# csi.net
KiCad netlist of a schematic drawn in Altium Designer
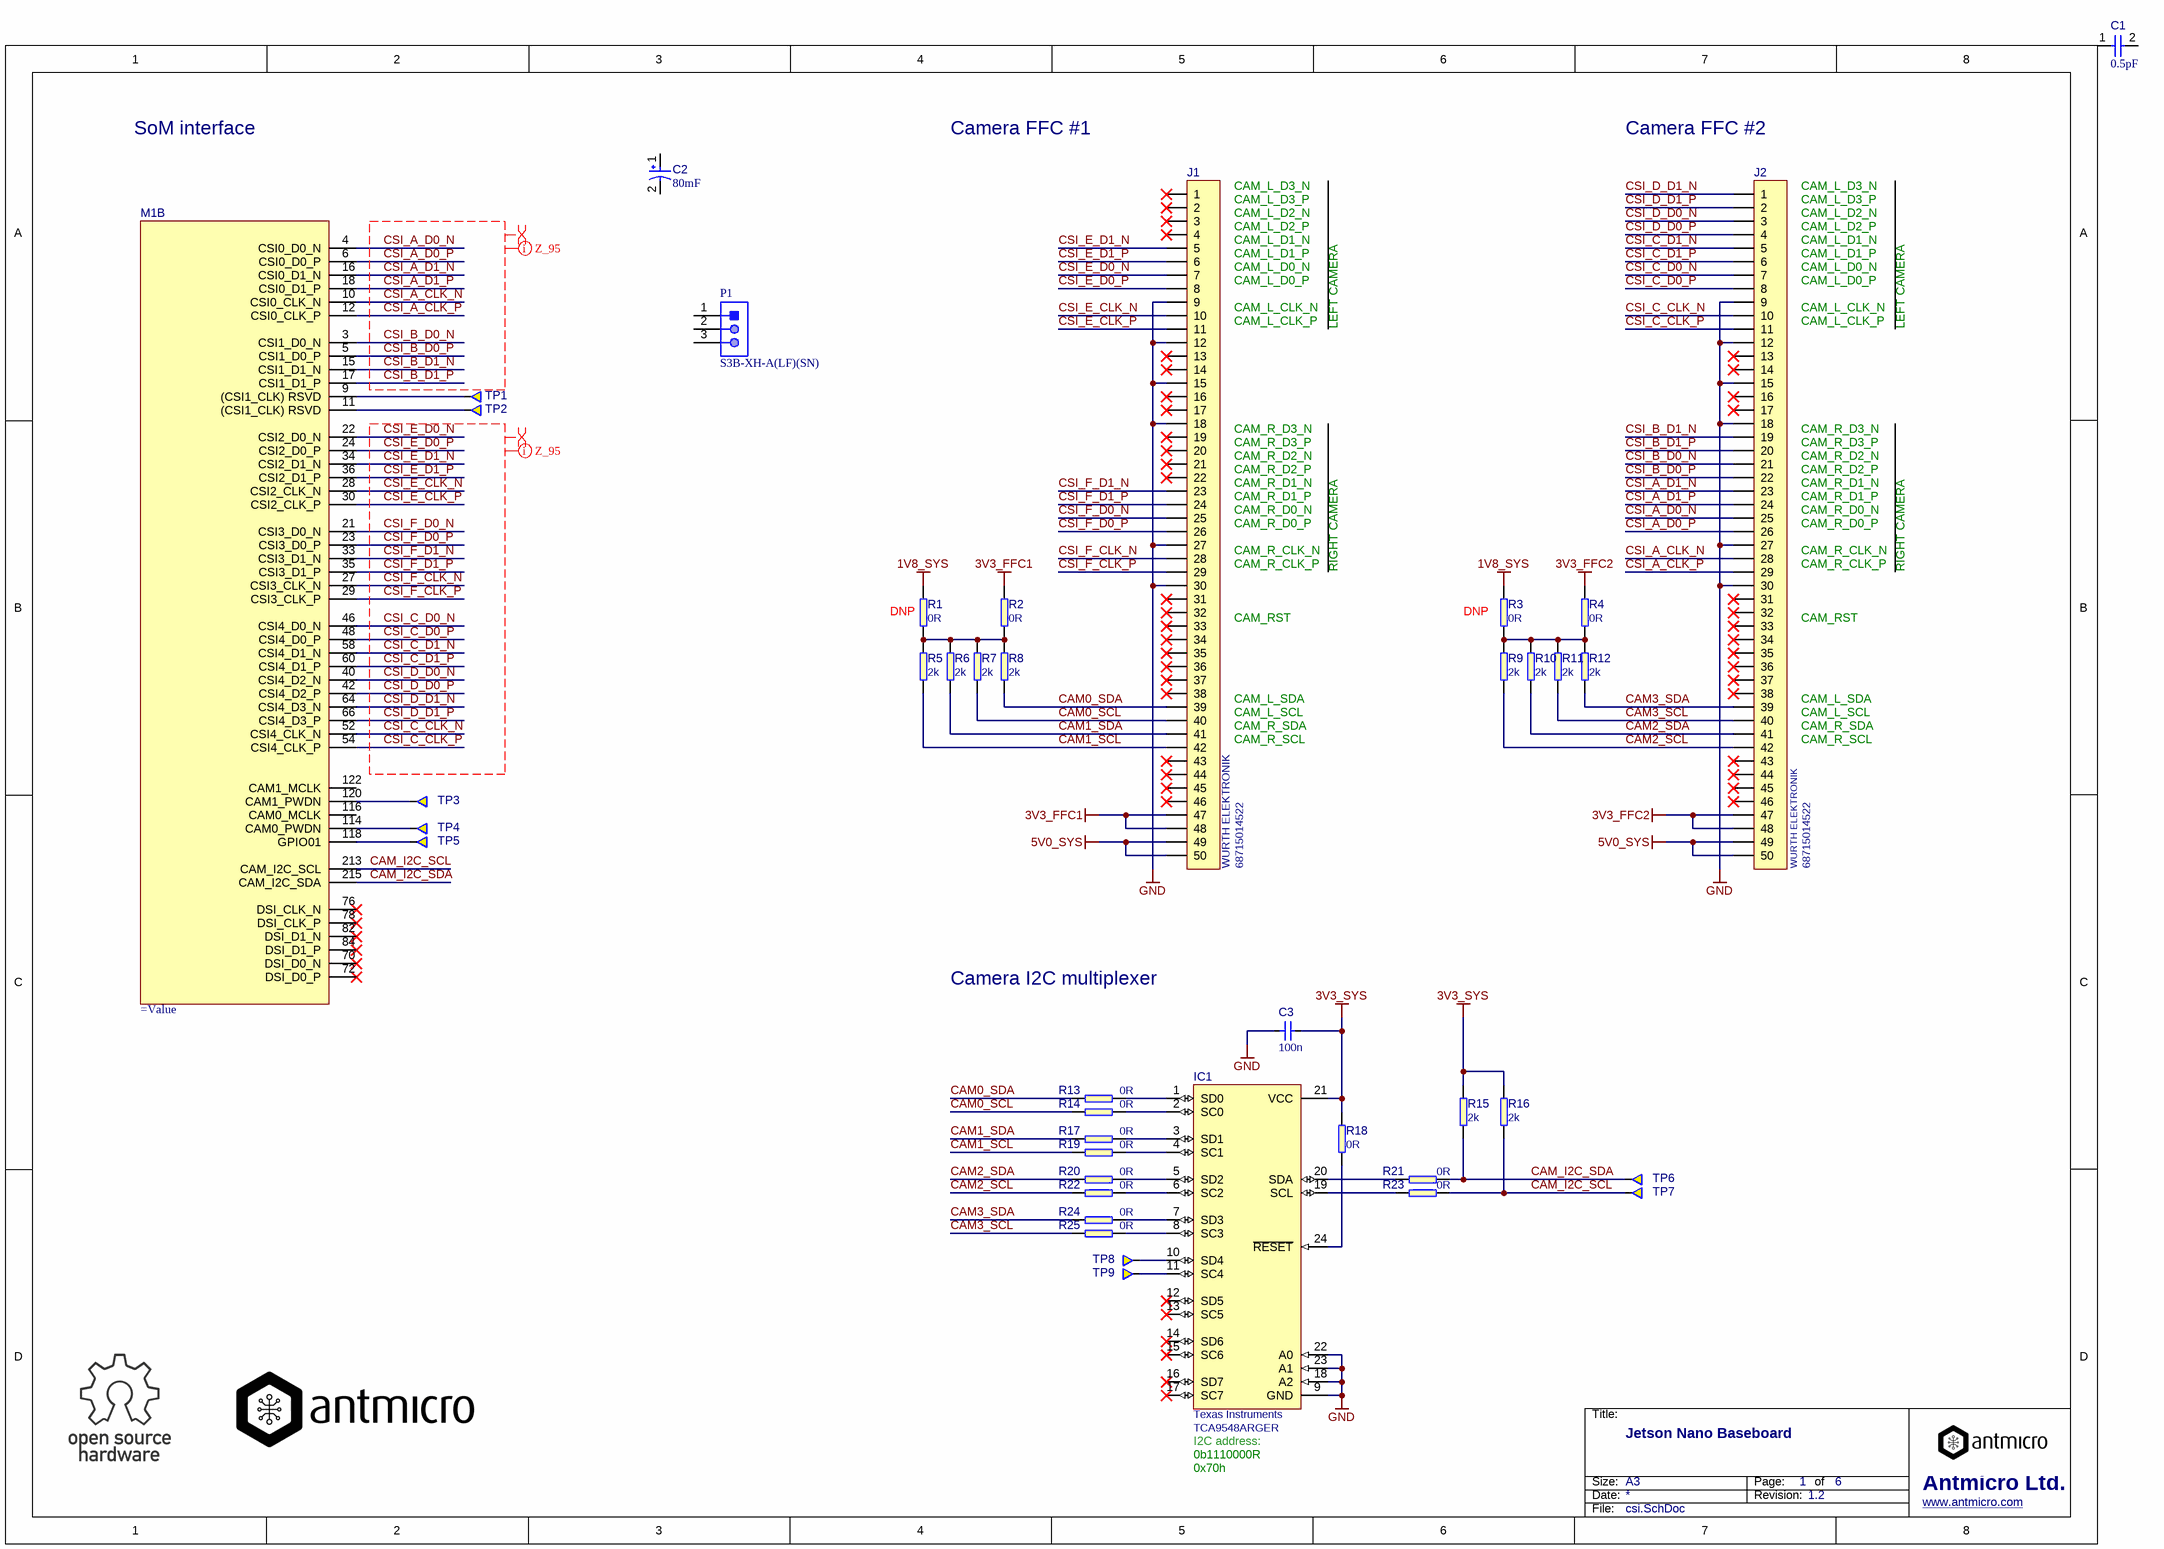
[diagram p0: csi.SchDoc]

(export (version "E")
  (design (tool "Eeschema 10.0.6"))
  (components
    (comp (ref "C1")
      (value "0.5pF")
      (footprint "CAPC1005X56X25ML10T15")
      (description "Chip Capacitor, 0.5 pF, +/- 0.1pF, 25 V, 0402 (1005 Metric)")
      (fields
        (field (name "TOLERANCE") "20%")
        (field (name "Comment") "Capacitor 0.5 pF +/- 0.1pF 25 V 0402")
      )
      (libsource (lib "ProtoTest2") (part "CAP-NP-2"))
    )
    (comp (ref "C2")
      (value "80mF")
      (footprint "SEIK-XH414HG-IV01E_V")
      (description "Electric Double Layer Capacitor, 80 mF, 3.3 V, -20 to 60 degC, RoHS")
      (fields (field (name "MANUFACTURER") "Seiko Instruments") (field (name "Comment") "XH414HG-IV01E"))
      (libsource (lib "ProtoTest2") (part "CAP-P-2"))
    )
    (comp (ref "C3")
      (value "100n")
      (footprint "0402")
      (description "MLCC SMT Capacitor 100n 0402")
      (fields (field (name "MANUFACTURER") "TDK") (field (name "PARTNUMBER") "C_100n_0402"))
      (libsource (lib "jetson-nano-baseboard") (part "C_100n_0402"))
    )
    (comp (ref "IC1")
      (value "TCA9548ARGER")
      (footprint "VQFN-24")
      (description "TCA9548ARGER  I2C SWITCH W/ RESET, 8-CH, VQFN-24")
      (fields (field (name "MANUFACTURER") "Texas Instruments"))
      (libsource (lib "jetson-nano-baseboard") (part "TCA9548A"))
    )
    (comp (ref "J1")
      (value "68715014522")
      (footprint "68715014522")
      (description "0.50mm SMT ZIF Horizontal Bottom Contact WR-FPC")
      (fields
        (field (name "MANUFACTURER") "WURTH ELEKTRONIK")
        (field (name "PARTNUMBER") "WE-687-150-145-22")
      )
      (libsource (lib "jetson-nano-baseboard") (part "1X50"))
    )
    (comp (ref "J2")
      (value "68715014522")
      (footprint "68715014522")
      (description "0.50mm SMT ZIF Horizontal Bottom Contact WR-FPC")
      (fields
        (field (name "PARTNUMBER") "WE-687-150-145-22")
        (field (name "MANUFACTURER") "WURTH ELEKTRONIK")
      )
      (libsource (lib "jetson-nano-baseboard") (part "1X50"))
    )
    (comp (ref "M1")
      (value "~")
      (footprint "jetson-nano-connector")
      (fields (field (name "PARTNUMBER") "jetson-nano-new-release"))
      (libsource (lib "jetson-nano-baseboard") (part "Jetson-Nano-new-release"))
    )
    (comp (ref "P1")
      (value "S3B-XH-A(LF)(SN)")
      (footprint "JST-S3B-XH-A(LF)(SN)_V")
      (fields (field (name "MANUFACTURER") "JST"))
      (libsource (lib "ProtoTest2") (part "CN-1P-M-R3"))
    )
    (comp (ref "R1")
      (value "0R")
      (footprint "0402")
      (description "RES, 0R, 0402")
      (fields (field (name "MANUFACTURER") "Panasonic") (field (name "PARTNUMBER") "R_0R_0402"))
      (libsource (lib "") (part "R_0R_0402_1"))
    )
    (comp (ref "R2")
      (value "0R")
      (footprint "0402")
      (description "RES, 0R, 0402")
      (fields (field (name "MANUFACTURER") "Panasonic") (field (name "PARTNUMBER") "R_0R_0402"))
      (libsource (lib "") (part "R_0R_0402_1"))
    )
    (comp (ref "R3")
      (value "0R")
      (footprint "0402")
      (description "RES, 0R, 0402")
      (fields (field (name "MANUFACTURER") "Panasonic") (field (name "PARTNUMBER") "R_0R_0402"))
      (libsource (lib "") (part "R_0R_0402_1"))
    )
    (comp (ref "R4")
      (value "0R")
      (footprint "0402")
      (description "RES, 0R, 0402")
      (fields (field (name "MANUFACTURER") "Panasonic") (field (name "PARTNUMBER") "R_0R_0402"))
      (libsource (lib "") (part "R_0R_0402_1"))
    )
    (comp (ref "R5")
      (value "2k")
      (footprint "0402")
      (description "RES, 2k, 0402")
      (fields (field (name "PARTNUMBER") "R_2k_0402") (field (name "MANUFACTURER") "VISHAY"))
      (libsource (lib "jetson-nano-baseboard") (part "R_2k_0402"))
    )
    (comp (ref "R6")
      (value "2k")
      (footprint "0402")
      (description "RES, 2k, 0402")
      (fields (field (name "PARTNUMBER") "R_2k_0402") (field (name "MANUFACTURER") "VISHAY"))
      (libsource (lib "jetson-nano-baseboard") (part "R_2k_0402"))
    )
    (comp (ref "R7")
      (value "2k")
      (footprint "0402")
      (description "RES, 2k, 0402")
      (fields (field (name "PARTNUMBER") "R_2k_0402") (field (name "MANUFACTURER") "VISHAY"))
      (libsource (lib "jetson-nano-baseboard") (part "R_2k_0402"))
    )
    (comp (ref "R8")
      (value "2k")
      (footprint "0402")
      (description "RES, 2k, 0402")
      (fields (field (name "PARTNUMBER") "R_2k_0402") (field (name "MANUFACTURER") "VISHAY"))
      (libsource (lib "jetson-nano-baseboard") (part "R_2k_0402"))
    )
    (comp (ref "R9")
      (value "2k")
      (footprint "0402")
      (description "RES, 2k, 0402")
      (fields (field (name "PARTNUMBER") "R_2k_0402") (field (name "MANUFACTURER") "VISHAY"))
      (libsource (lib "jetson-nano-baseboard") (part "R_2k_0402"))
    )
    (comp (ref "R10")
      (value "2k")
      (footprint "0402")
      (description "RES, 2k, 0402")
      (fields (field (name "PARTNUMBER") "R_2k_0402") (field (name "MANUFACTURER") "VISHAY"))
      (libsource (lib "jetson-nano-baseboard") (part "R_2k_0402"))
    )
    (comp (ref "R11")
      (value "2k")
      (footprint "0402")
      (description "RES, 2k, 0402")
      (fields (field (name "PARTNUMBER") "R_2k_0402") (field (name "MANUFACTURER") "VISHAY"))
      (libsource (lib "jetson-nano-baseboard") (part "R_2k_0402"))
    )
    (comp (ref "R12")
      (value "2k")
      (footprint "0402")
      (description "RES, 2k, 0402")
      (fields (field (name "PARTNUMBER") "R_2k_0402") (field (name "MANUFACTURER") "VISHAY"))
      (libsource (lib "jetson-nano-baseboard") (part "R_2k_0402"))
    )
    (comp (ref "R13")
      (value "0R")
      (footprint "0402")
      (description "RES, 0R, 0402")
      (fields (field (name "MANUFACTURER") "Panasonic") (field (name "PARTNUMBER") "R_0R_0402"))
      (libsource (lib "jetson-nano-baseboard") (part "R_0R_0402"))
    )
    (comp (ref "R14")
      (value "0R")
      (footprint "0402")
      (description "RES, 0R, 0402")
      (fields (field (name "MANUFACTURER") "Panasonic") (field (name "PARTNUMBER") "R_0R_0402"))
      (libsource (lib "jetson-nano-baseboard") (part "R_0R_0402"))
    )
    (comp (ref "R15")
      (value "2k")
      (footprint "0402")
      (description "RES, 2k, 0402")
      (fields (field (name "PARTNUMBER") "R_2k_0402") (field (name "MANUFACTURER") "VISHAY"))
      (libsource (lib "jetson-nano-baseboard") (part "R_2k_0402"))
    )
    (comp (ref "R16")
      (value "2k")
      (footprint "0402")
      (description "RES, 2k, 0402")
      (fields (field (name "PARTNUMBER") "R_2k_0402") (field (name "MANUFACTURER") "VISHAY"))
      (libsource (lib "jetson-nano-baseboard") (part "R_2k_0402"))
    )
    (comp (ref "R17")
      (value "0R")
      (footprint "0402")
      (description "RES, 0R, 0402")
      (fields (field (name "MANUFACTURER") "Panasonic") (field (name "PARTNUMBER") "R_0R_0402"))
      (libsource (lib "jetson-nano-baseboard") (part "R_0R_0402"))
    )
    (comp (ref "R18")
      (value "0R")
      (footprint "0402")
      (description "RES, 0R, 0402")
      (fields (field (name "MANUFACTURER") "Panasonic") (field (name "PARTNUMBER") "R_0R_0402"))
      (libsource (lib "") (part "R_0R_0402_1"))
    )
    (comp (ref "R19")
      (value "0R")
      (footprint "0402")
      (description "RES, 0R, 0402")
      (fields (field (name "MANUFACTURER") "Panasonic") (field (name "PARTNUMBER") "R_0R_0402"))
      (libsource (lib "jetson-nano-baseboard") (part "R_0R_0402"))
    )
    (comp (ref "R20")
      (value "0R")
      (footprint "0402")
      (description "RES, 0R, 0402")
      (fields (field (name "MANUFACTURER") "Panasonic") (field (name "PARTNUMBER") "R_0R_0402"))
      (libsource (lib "jetson-nano-baseboard") (part "R_0R_0402"))
    )
    (comp (ref "R21")
      (value "0R")
      (footprint "0402")
      (description "RES, 0R, 0402")
      (fields (field (name "MANUFACTURER") "Panasonic") (field (name "PARTNUMBER") "R_0R_0402"))
      (libsource (lib "jetson-nano-baseboard") (part "R_0R_0402"))
    )
    (comp (ref "R22")
      (value "0R")
      (footprint "0402")
      (description "RES, 0R, 0402")
      (fields (field (name "MANUFACTURER") "Panasonic") (field (name "PARTNUMBER") "R_0R_0402"))
      (libsource (lib "jetson-nano-baseboard") (part "R_0R_0402"))
    )
    (comp (ref "R23")
      (value "0R")
      (footprint "0402")
      (description "RES, 0R, 0402")
      (fields (field (name "MANUFACTURER") "Panasonic") (field (name "PARTNUMBER") "R_0R_0402"))
      (libsource (lib "jetson-nano-baseboard") (part "R_0R_0402"))
    )
    (comp (ref "R24")
      (value "0R")
      (footprint "0402")
      (description "RES, 0R, 0402")
      (fields (field (name "MANUFACTURER") "Panasonic") (field (name "PARTNUMBER") "R_0R_0402"))
      (libsource (lib "jetson-nano-baseboard") (part "R_0R_0402"))
    )
    (comp (ref "R25")
      (value "0R")
      (footprint "0402")
      (description "RES, 0R, 0402")
      (fields (field (name "MANUFACTURER") "Panasonic") (field (name "PARTNUMBER") "R_0R_0402"))
      (libsource (lib "jetson-nano-baseboard") (part "R_0R_0402"))
    )
    (comp (ref "TP1")
      (value "Testpad")
      (footprint "TP-R-1.5")
      (description "Testpad, round, 1.5mm")
      (fields (field (name "PARTNUMBER") "TP-R-1.5"))
      (libsource (lib "jetson-nano-baseboard") (part "Testpad"))
    )
    (comp (ref "TP2")
      (value "Testpad")
      (footprint "TP-R-1.5")
      (description "Testpad, round, 1.5mm")
      (fields (field (name "PARTNUMBER") "TP-R-1.5"))
      (libsource (lib "jetson-nano-baseboard") (part "Testpad"))
    )
    (comp (ref "TP3")
      (value "Testpad")
      (footprint "TP-R-1.5")
      (description "Testpad, round, 1.5mm")
      (fields (field (name "PARTNUMBER") "TP-R-1.5"))
      (libsource (lib "jetson-nano-baseboard") (part "Testpad"))
    )
    (comp (ref "TP4")
      (value "Testpad")
      (footprint "TP-R-1.5")
      (description "Testpad, round, 1.5mm")
      (fields (field (name "PARTNUMBER") "TP-R-1.5"))
      (libsource (lib "jetson-nano-baseboard") (part "Testpad"))
    )
    (comp (ref "TP5")
      (value "Testpad")
      (footprint "TP-R-1.5")
      (description "Testpad, round, 1.5mm")
      (fields (field (name "PARTNUMBER") "TP-R-1.5"))
      (libsource (lib "jetson-nano-baseboard") (part "Testpad"))
    )
    (comp (ref "TP6")
      (value "Testpad")
      (footprint "TP-R-1.5")
      (description "Testpad, round, 1.5mm")
      (fields (field (name "PARTNUMBER") "TP-R-1.5"))
      (libsource (lib "jetson-nano-baseboard") (part "Testpad"))
    )
    (comp (ref "TP7")
      (value "Testpad")
      (footprint "TP-R-1.5")
      (description "Testpad, round, 1.5mm")
      (fields (field (name "PARTNUMBER") "TP-R-1.5"))
      (libsource (lib "jetson-nano-baseboard") (part "Testpad"))
    )
    (comp (ref "TP8")
      (value "Testpad")
      (footprint "TP-R-1.5")
      (description "Testpad, round, 1.5mm")
      (fields (field (name "PARTNUMBER") "TP-R-1.5"))
      (libsource (lib "jetson-nano-baseboard") (part "Testpad"))
    )
    (comp (ref "TP9")
      (value "Testpad")
      (footprint "TP-R-1.5")
      (description "Testpad, round, 1.5mm")
      (fields (field (name "PARTNUMBER") "TP-R-1.5"))
      (libsource (lib "jetson-nano-baseboard") (part "Testpad"))
    )
  )
  (nets
    (net (code "1") (name "/CAM0_SCL") (class "Default")
      (node (ref "J1") (pin "40") (pinfunction "40_40") (pintype "passive"))
      (node (ref "R14") (pin "1") (pintype "passive"))
      (node (ref "R7") (pin "2") (pintype "passive"))
    )
    (net (code "2") (name "/CAM0_SDA") (class "Default")
      (node (ref "J1") (pin "39") (pinfunction "39_39") (pintype "passive"))
      (node (ref "R13") (pin "1") (pintype "passive"))
      (node (ref "R8") (pin "2") (pintype "passive"))
    )
    (net (code "3") (name "/CAM1_SCL") (class "Default")
      (node (ref "J1") (pin "42") (pinfunction "42_42") (pintype "passive"))
      (node (ref "R19") (pin "1") (pintype "passive"))
      (node (ref "R5") (pin "2") (pintype "passive"))
    )
    (net (code "4") (name "/CAM1_SDA") (class "Default")
      (node (ref "J1") (pin "41") (pinfunction "41_41") (pintype "passive"))
      (node (ref "R17") (pin "1") (pintype "passive"))
      (node (ref "R6") (pin "2") (pintype "passive"))
    )
    (net (code "5") (name "/CAM2_SCL") (class "Default")
      (node (ref "J2") (pin "42") (pinfunction "42_42") (pintype "passive"))
      (node (ref "R22") (pin "1") (pintype "passive"))
      (node (ref "R9") (pin "2") (pintype "passive"))
    )
    (net (code "6") (name "/CAM2_SDA") (class "Default")
      (node (ref "J2") (pin "41") (pinfunction "41_41") (pintype "passive"))
      (node (ref "R10") (pin "2") (pintype "passive"))
      (node (ref "R20") (pin "1") (pintype "passive"))
    )
    (net (code "7") (name "/CAM3_SCL") (class "Default")
      (node (ref "J2") (pin "40") (pinfunction "40_40") (pintype "passive"))
      (node (ref "R11") (pin "2") (pintype "passive"))
      (node (ref "R25") (pin "1") (pintype "passive"))
    )
    (net (code "8") (name "/CAM3_SDA") (class "Default")
      (node (ref "J2") (pin "39") (pinfunction "39_39") (pintype "passive"))
      (node (ref "R12") (pin "2") (pintype "passive"))
      (node (ref "R24") (pin "1") (pintype "passive"))
    )
    (net (code "9") (name "/CAM_I2C_SCL") (class "Default")
      (node (ref "M1") (pin "213") (pinfunction "CAM_I2C_SCL_213") (pintype "passive"))
      (node (ref "R16") (pin "2") (pintype "passive"))
      (node (ref "R23") (pin "2") (pintype "passive"))
      (node (ref "TP7") (pin "1") (pintype "passive"))
    )
    (net (code "10") (name "/CAM_I2C_SDA") (class "Default")
      (node (ref "M1") (pin "215") (pinfunction "CAM_I2C_SDA_215") (pintype "passive"))
      (node (ref "R15") (pin "2") (pintype "passive"))
      (node (ref "R21") (pin "2") (pintype "passive"))
      (node (ref "TP6") (pin "1") (pintype "passive"))
    )
    (net (code "11") (name "/CSI_A_CLK_N") (class "Default")
      (node (ref "J2") (pin "28") (pinfunction "28_28") (pintype "passive"))
      (node (ref "M1") (pin "10") (pinfunction "CSI0_CLK_N_10") (pintype "passive"))
    )
    (net (code "12") (name "/CSI_A_CLK_P") (class "Default")
      (node (ref "J2") (pin "29") (pinfunction "29_29") (pintype "passive"))
      (node (ref "M1") (pin "12") (pinfunction "CSI0_CLK_P_12") (pintype "passive"))
    )
    (net (code "13") (name "/CSI_A_D0_N") (class "Default")
      (node (ref "J2") (pin "25") (pinfunction "25_25") (pintype "passive"))
      (node (ref "M1") (pin "4") (pinfunction "CSI0_D0_N_4") (pintype "passive"))
    )
    (net (code "14") (name "/CSI_A_D0_P") (class "Default")
      (node (ref "J2") (pin "26") (pinfunction "26_26") (pintype "passive"))
      (node (ref "M1") (pin "6") (pinfunction "CSI0_D0_P_6") (pintype "passive"))
    )
    (net (code "15") (name "/CSI_A_D1_N") (class "Default")
      (node (ref "J2") (pin "23") (pinfunction "23_23") (pintype "passive"))
      (node (ref "M1") (pin "16") (pinfunction "CSI0_D1_N_16") (pintype "passive"))
    )
    (net (code "16") (name "/CSI_A_D1_P") (class "Default")
      (node (ref "J2") (pin "24") (pinfunction "24_24") (pintype "passive"))
      (node (ref "M1") (pin "18") (pinfunction "CSI0_D1_P_18") (pintype "passive"))
    )
    (net (code "17") (name "/CSI_B_D0_N") (class "Default")
      (node (ref "J2") (pin "21") (pinfunction "21_21") (pintype "passive"))
      (node (ref "M1") (pin "3") (pinfunction "CSI1_D0_N_3") (pintype "passive"))
    )
    (net (code "18") (name "/CSI_B_D0_P") (class "Default")
      (node (ref "J2") (pin "22") (pinfunction "22_22") (pintype "passive"))
      (node (ref "M1") (pin "5") (pinfunction "CSI1_D0_P_5") (pintype "passive"))
    )
    (net (code "19") (name "/CSI_B_D1_N") (class "Default")
      (node (ref "J2") (pin "19") (pinfunction "19_19") (pintype "passive"))
      (node (ref "M1") (pin "15") (pinfunction "CSI1_D1_N_15") (pintype "passive"))
    )
    (net (code "20") (name "/CSI_B_D1_P") (class "Default")
      (node (ref "J2") (pin "20") (pinfunction "20_20") (pintype "passive"))
      (node (ref "M1") (pin "17") (pinfunction "CSI1_D1_P_17") (pintype "passive"))
    )
    (net (code "21") (name "/CSI_C_CLK_N") (class "Default")
      (node (ref "J2") (pin "10") (pinfunction "10_10") (pintype "passive"))
      (node (ref "M1") (pin "52") (pinfunction "CSI4_CLK_N_52") (pintype "passive"))
    )
    (net (code "22") (name "/CSI_C_CLK_P") (class "Default")
      (node (ref "J2") (pin "11") (pinfunction "11_11") (pintype "passive"))
      (node (ref "M1") (pin "54") (pinfunction "CSI4_CLK_P_54") (pintype "passive"))
    )
    (net (code "23") (name "/CSI_C_D0_N") (class "Default")
      (node (ref "J2") (pin "7") (pinfunction "7_7") (pintype "passive"))
      (node (ref "M1") (pin "46") (pinfunction "CSI4_D0_N_46") (pintype "passive"))
    )
    (net (code "24") (name "/CSI_C_D0_P") (class "Default")
      (node (ref "J2") (pin "8") (pinfunction "8_8") (pintype "passive"))
      (node (ref "M1") (pin "48") (pinfunction "CSI4_D0_P_48") (pintype "passive"))
    )
    (net (code "25") (name "/CSI_C_D1_N") (class "Default")
      (node (ref "J2") (pin "5") (pinfunction "5_5") (pintype "passive"))
      (node (ref "M1") (pin "58") (pinfunction "CSI4_D1_N_58") (pintype "passive"))
    )
    (net (code "26") (name "/CSI_C_D1_P") (class "Default")
      (node (ref "J2") (pin "6") (pinfunction "6_6") (pintype "passive"))
      (node (ref "M1") (pin "60") (pinfunction "CSI4_D1_P_60") (pintype "passive"))
    )
    (net (code "27") (name "/CSI_D_D0_N") (class "Default")
      (node (ref "J2") (pin "3") (pinfunction "3_3") (pintype "passive"))
      (node (ref "M1") (pin "40") (pinfunction "CSI4_D2_N_40") (pintype "passive"))
    )
    (net (code "28") (name "/CSI_D_D0_P") (class "Default")
      (node (ref "J2") (pin "4") (pinfunction "4_4") (pintype "passive"))
      (node (ref "M1") (pin "42") (pinfunction "CSI4_D2_P_42") (pintype "passive"))
    )
    (net (code "29") (name "/CSI_D_D1_N") (class "Default")
      (node (ref "J2") (pin "1") (pinfunction "1_1") (pintype "passive"))
      (node (ref "M1") (pin "64") (pinfunction "CSI4_D3_N_64") (pintype "passive"))
    )
    (net (code "30") (name "/CSI_D_D1_P") (class "Default")
      (node (ref "J2") (pin "2") (pinfunction "2_2") (pintype "passive"))
      (node (ref "M1") (pin "66") (pinfunction "CSI4_D3_P_66") (pintype "passive"))
    )
    (net (code "31") (name "/CSI_E_CLK_N") (class "Default")
      (node (ref "J1") (pin "10") (pinfunction "10_10") (pintype "passive"))
      (node (ref "M1") (pin "28") (pinfunction "CSI2_CLK_N_28") (pintype "passive"))
    )
    (net (code "32") (name "/CSI_E_CLK_P") (class "Default")
      (node (ref "J1") (pin "11") (pinfunction "11_11") (pintype "passive"))
      (node (ref "M1") (pin "30") (pinfunction "CSI2_CLK_P_30") (pintype "passive"))
    )
    (net (code "33") (name "/CSI_E_D0_N") (class "Default")
      (node (ref "J1") (pin "7") (pinfunction "7_7") (pintype "passive"))
      (node (ref "M1") (pin "22") (pinfunction "CSI2_D0_N_22") (pintype "passive"))
    )
    (net (code "34") (name "/CSI_E_D0_P") (class "Default")
      (node (ref "J1") (pin "8") (pinfunction "8_8") (pintype "passive"))
      (node (ref "M1") (pin "24") (pinfunction "CSI2_D0_P_24") (pintype "passive"))
    )
    (net (code "35") (name "/CSI_E_D1_N") (class "Default")
      (node (ref "J1") (pin "5") (pinfunction "5_5") (pintype "passive"))
      (node (ref "M1") (pin "34") (pinfunction "CSI2_D1_N_34") (pintype "passive"))
    )
    (net (code "36") (name "/CSI_E_D1_P") (class "Default")
      (node (ref "J1") (pin "6") (pinfunction "6_6") (pintype "passive"))
      (node (ref "M1") (pin "36") (pinfunction "CSI2_D1_P_36") (pintype "passive"))
    )
    (net (code "37") (name "/CSI_F_CLK_N") (class "Default")
      (node (ref "J1") (pin "28") (pinfunction "28_28") (pintype "passive"))
      (node (ref "M1") (pin "27") (pinfunction "CSI3_CLK_N_27") (pintype "passive"))
    )
    (net (code "38") (name "/CSI_F_CLK_P") (class "Default")
      (node (ref "J1") (pin "29") (pinfunction "29_29") (pintype "passive"))
      (node (ref "M1") (pin "29") (pinfunction "CSI3_CLK_P_29") (pintype "passive"))
    )
    (net (code "39") (name "/CSI_F_D0_N") (class "Default")
      (node (ref "J1") (pin "25") (pinfunction "25_25") (pintype "passive"))
      (node (ref "M1") (pin "21") (pinfunction "CSI3_D0_N_21") (pintype "passive"))
    )
    (net (code "40") (name "/CSI_F_D0_P") (class "Default")
      (node (ref "J1") (pin "26") (pinfunction "26_26") (pintype "passive"))
      (node (ref "M1") (pin "23") (pinfunction "CSI3_D0_P_23") (pintype "passive"))
    )
    (net (code "41") (name "/CSI_F_D1_N") (class "Default")
      (node (ref "J1") (pin "23") (pinfunction "23_23") (pintype "passive"))
      (node (ref "M1") (pin "33") (pinfunction "CSI3_D1_N_33") (pintype "passive"))
    )
    (net (code "42") (name "/CSI_F_D1_P") (class "Default")
      (node (ref "J1") (pin "24") (pinfunction "24_24") (pintype "passive"))
      (node (ref "M1") (pin "35") (pinfunction "CSI3_D1_P_35") (pintype "passive"))
    )
    (net (code "43") (name "1V8_SYS") (class "Default")
      (node (ref "R1") (pin "2") (pintype "passive"))
      (node (ref "R3") (pin "2") (pintype "passive"))
    )
    (net (code "44") (name "3V3_FFC1") (class "Default")
      (node (ref "J1") (pin "47") (pinfunction "47_47") (pintype "passive"))
      (node (ref "J1") (pin "48") (pinfunction "48_48") (pintype "passive"))
      (node (ref "R2") (pin "2") (pintype "passive"))
    )
    (net (code "45") (name "3V3_FFC2") (class "Default")
      (node (ref "J2") (pin "47") (pinfunction "47_47") (pintype "passive"))
      (node (ref "J2") (pin "48") (pinfunction "48_48") (pintype "passive"))
      (node (ref "R4") (pin "2") (pintype "passive"))
    )
    (net (code "46") (name "3V3_SYS") (class "Default")
      (node (ref "C3") (pin "2") (pinfunction "2_2") (pintype "passive"))
      (node (ref "IC1") (pin "21") (pinfunction "VCC_21") (pintype "power_in"))
      (node (ref "R15") (pin "1") (pintype "passive"))
      (node (ref "R16") (pin "1") (pintype "passive"))
      (node (ref "R18") (pin "2") (pintype "passive"))
    )
    (net (code "47") (name "5V0_SYS") (class "Default")
      (node (ref "J1") (pin "49") (pinfunction "49_49") (pintype "passive"))
      (node (ref "J1") (pin "50") (pinfunction "50_50") (pintype "passive"))
      (node (ref "J2") (pin "49") (pinfunction "49_49") (pintype "passive"))
      (node (ref "J2") (pin "50") (pinfunction "50_50") (pintype "passive"))
    )
    (net (code "48") (name "GND") (class "Default")
      (node (ref "C3") (pin "1") (pinfunction "1_1") (pintype "passive"))
      (node (ref "IC1") (pin "18") (pinfunction "A2_18") (pintype "input"))
      (node (ref "IC1") (pin "22") (pinfunction "A0_22") (pintype "input"))
      (node (ref "IC1") (pin "23") (pinfunction "A1_23") (pintype "input"))
      (node (ref "IC1") (pin "9") (pinfunction "GND_9") (pintype "power_in"))
      (node (ref "J1") (pin "12") (pinfunction "12_12") (pintype "passive"))
      (node (ref "J1") (pin "15") (pinfunction "15_15") (pintype "passive"))
      (node (ref "J1") (pin "18") (pinfunction "18_18") (pintype "passive"))
      (node (ref "J1") (pin "27") (pinfunction "27_27") (pintype "passive"))
      (node (ref "J1") (pin "30") (pinfunction "30_30") (pintype "passive"))
      (node (ref "J1") (pin "9") (pinfunction "9_9") (pintype "passive"))
      (node (ref "J2") (pin "12") (pinfunction "12_12") (pintype "passive"))
      (node (ref "J2") (pin "15") (pinfunction "15_15") (pintype "passive"))
      (node (ref "J2") (pin "18") (pinfunction "18_18") (pintype "passive"))
      (node (ref "J2") (pin "27") (pinfunction "27_27") (pintype "passive"))
      (node (ref "J2") (pin "30") (pinfunction "30_30") (pintype "passive"))
      (node (ref "J2") (pin "9") (pinfunction "9_9") (pintype "passive"))
    )
    (net (code "49") (name "Net-(IC1-SC0)") (class "Default")
      (node (ref "IC1") (pin "2") (pinfunction "SC0_2") (pintype "bidirectional"))
      (node (ref "R14") (pin "2") (pintype "passive"))
    )
    (net (code "50") (name "Net-(IC1-SC1)") (class "Default")
      (node (ref "IC1") (pin "4") (pinfunction "SC1_4") (pintype "bidirectional"))
      (node (ref "R19") (pin "2") (pintype "passive"))
    )
    (net (code "51") (name "Net-(IC1-SC2)") (class "Default")
      (node (ref "IC1") (pin "6") (pinfunction "SC2_6") (pintype "bidirectional"))
      (node (ref "R22") (pin "2") (pintype "passive"))
    )
    (net (code "52") (name "Net-(IC1-SC3)") (class "Default")
      (node (ref "IC1") (pin "8") (pinfunction "SC3_8") (pintype "bidirectional"))
      (node (ref "R25") (pin "2") (pintype "passive"))
    )
    (net (code "53") (name "Net-(IC1-SC4)") (class "Default")
      (node (ref "IC1") (pin "11") (pinfunction "SC4_11") (pintype "bidirectional"))
      (node (ref "TP9") (pin "1") (pintype "passive"))
    )
    (net (code "54") (name "Net-(IC1-SCL)") (class "Default")
      (node (ref "IC1") (pin "19") (pinfunction "SCL_19") (pintype "bidirectional"))
      (node (ref "R23") (pin "1") (pintype "passive"))
    )
    (net (code "55") (name "Net-(IC1-SD0)") (class "Default")
      (node (ref "IC1") (pin "1") (pinfunction "SD0_1") (pintype "bidirectional"))
      (node (ref "R13") (pin "2") (pintype "passive"))
    )
    (net (code "56") (name "Net-(IC1-SD1)") (class "Default")
      (node (ref "IC1") (pin "3") (pinfunction "SD1_3") (pintype "bidirectional"))
      (node (ref "R17") (pin "2") (pintype "passive"))
    )
    (net (code "57") (name "Net-(IC1-SD2)") (class "Default")
      (node (ref "IC1") (pin "5") (pinfunction "SD2_5") (pintype "bidirectional"))
      (node (ref "R20") (pin "2") (pintype "passive"))
    )
    (net (code "58") (name "Net-(IC1-SD3)") (class "Default")
      (node (ref "IC1") (pin "7") (pinfunction "SD3_7") (pintype "bidirectional"))
      (node (ref "R24") (pin "2") (pintype "passive"))
    )
    (net (code "59") (name "Net-(IC1-SD4)") (class "Default")
      (node (ref "IC1") (pin "10") (pinfunction "SD4_10") (pintype "bidirectional"))
      (node (ref "TP8") (pin "1") (pintype "passive"))
    )
    (net (code "60") (name "Net-(IC1-SDA)") (class "Default")
      (node (ref "IC1") (pin "20") (pinfunction "SDA_20") (pintype "bidirectional"))
      (node (ref "R21") (pin "1") (pintype "passive"))
    )
    (net (code "61") (name "Net-(IC1-~{RESET})") (class "Default")
      (node (ref "IC1") (pin "24") (pinfunction "~{RESET}_24") (pintype "input"))
      (node (ref "R18") (pin "1") (pintype "passive"))
    )
    (net (code "62") (name "Net-(M1B-(CSI1_CLK)_RSVD-Pad9)") (class "Default")
      (node (ref "M1") (pin "9") (pinfunction "(CSI1_CLK)_RSVD_9") (pintype "passive"))
      (node (ref "TP1") (pin "1") (pintype "passive"))
    )
    (net (code "63") (name "Net-(M1B-(CSI1_CLK)_RSVD-Pad11)") (class "Default")
      (node (ref "M1") (pin "11") (pinfunction "(CSI1_CLK)_RSVD_11") (pintype "passive"))
      (node (ref "TP2") (pin "1") (pintype "passive"))
    )
    (net (code "64") (name "Net-(M1B-CAM0_PWDN)") (class "Default")
      (node (ref "M1") (pin "114") (pinfunction "CAM0_PWDN_114") (pintype "passive"))
      (node (ref "TP4") (pin "1") (pintype "passive"))
    )
    (net (code "65") (name "Net-(M1B-CAM1_PWDN)") (class "Default")
      (node (ref "M1") (pin "120") (pinfunction "CAM1_PWDN_120") (pintype "passive"))
      (node (ref "TP3") (pin "1") (pintype "passive"))
    )
    (net (code "66") (name "Net-(M1B-GPIO01)") (class "Default")
      (node (ref "M1") (pin "118") (pinfunction "GPIO01_118") (pintype "passive"))
      (node (ref "TP5") (pin "1") (pintype "passive"))
    )
    (net (code "67") (name "Net-(R1-Pad1)") (class "Default")
      (node (ref "R1") (pin "1") (pintype "passive"))
      (node (ref "R2") (pin "1") (pintype "passive"))
      (node (ref "R5") (pin "1") (pintype "passive"))
      (node (ref "R6") (pin "1") (pintype "passive"))
      (node (ref "R7") (pin "1") (pintype "passive"))
      (node (ref "R8") (pin "1") (pintype "passive"))
    )
    (net (code "68") (name "Net-(R10-Pad1)") (class "Default")
      (node (ref "R10") (pin "1") (pintype "passive"))
      (node (ref "R11") (pin "1") (pintype "passive"))
      (node (ref "R12") (pin "1") (pintype "passive"))
      (node (ref "R3") (pin "1") (pintype "passive"))
      (node (ref "R4") (pin "1") (pintype "passive"))
      (node (ref "R9") (pin "1") (pintype "passive"))
    )
    (net (code "69") (name "unconnected-(C1-Pad1)") (class "Default")
      (node (ref "C1") (pin "1") (pinfunction "1_1") (pintype "passive"))
    )
    (net (code "70") (name "unconnected-(C1-Pad2)") (class "Default")
      (node (ref "C1") (pin "2") (pinfunction "2_2") (pintype "passive"))
    )
    (net (code "71") (name "unconnected-(C2-Pad1)") (class "Default")
      (node (ref "C2") (pin "1") (pinfunction "1_1") (pintype "passive"))
    )
    (net (code "72") (name "unconnected-(C2-Pad2)") (class "Default")
      (node (ref "C2") (pin "2") (pinfunction "2_2") (pintype "passive"))
    )
    (net (code "73") (name "unconnected-(IC1-SC5-Pad13)") (class "Default")
      (node (ref "IC1") (pin "13") (pinfunction "SC5_13") (pintype "bidirectional+no_connect"))
    )
    (net (code "74") (name "unconnected-(IC1-SC6-Pad15)") (class "Default")
      (node (ref "IC1") (pin "15") (pinfunction "SC6_15") (pintype "bidirectional+no_connect"))
    )
    (net (code "75") (name "unconnected-(IC1-SC7-Pad17)") (class "Default")
      (node (ref "IC1") (pin "17") (pinfunction "SC7_17") (pintype "bidirectional+no_connect"))
    )
    (net (code "76") (name "unconnected-(IC1-SD5-Pad12)") (class "Default")
      (node (ref "IC1") (pin "12") (pinfunction "SD5_12") (pintype "bidirectional+no_connect"))
    )
    (net (code "77") (name "unconnected-(IC1-SD6-Pad14)") (class "Default")
      (node (ref "IC1") (pin "14") (pinfunction "SD6_14") (pintype "bidirectional+no_connect"))
    )
    (net (code "78") (name "unconnected-(IC1-SD7-Pad16)") (class "Default")
      (node (ref "IC1") (pin "16") (pinfunction "SD7_16") (pintype "bidirectional+no_connect"))
    )
    (net (code "79") (name "unconnected-(J1-Pad1)") (class "Default")
      (node (ref "J1") (pin "1") (pinfunction "1_1") (pintype "passive+no_connect"))
    )
    (net (code "80") (name "unconnected-(J1-Pad2)") (class "Default")
      (node (ref "J1") (pin "2") (pinfunction "2_2") (pintype "passive+no_connect"))
    )
    (net (code "81") (name "unconnected-(J1-Pad3)") (class "Default")
      (node (ref "J1") (pin "3") (pinfunction "3_3") (pintype "passive+no_connect"))
    )
    (net (code "82") (name "unconnected-(J1-Pad4)") (class "Default")
      (node (ref "J1") (pin "4") (pinfunction "4_4") (pintype "passive+no_connect"))
    )
    (net (code "83") (name "unconnected-(J1-Pad13)") (class "Default")
      (node (ref "J1") (pin "13") (pinfunction "13_13") (pintype "passive+no_connect"))
    )
    (net (code "84") (name "unconnected-(J1-Pad14)") (class "Default")
      (node (ref "J1") (pin "14") (pinfunction "14_14") (pintype "passive+no_connect"))
    )
    (net (code "85") (name "unconnected-(J1-Pad16)") (class "Default")
      (node (ref "J1") (pin "16") (pinfunction "16_16") (pintype "passive+no_connect"))
    )
    (net (code "86") (name "unconnected-(J1-Pad17)") (class "Default")
      (node (ref "J1") (pin "17") (pinfunction "17_17") (pintype "passive+no_connect"))
    )
    (net (code "87") (name "unconnected-(J1-Pad19)") (class "Default")
      (node (ref "J1") (pin "19") (pinfunction "19_19") (pintype "passive+no_connect"))
    )
    (net (code "88") (name "unconnected-(J1-Pad20)") (class "Default")
      (node (ref "J1") (pin "20") (pinfunction "20_20") (pintype "passive+no_connect"))
    )
    (net (code "89") (name "unconnected-(J1-Pad21)") (class "Default")
      (node (ref "J1") (pin "21") (pinfunction "21_21") (pintype "passive+no_connect"))
    )
    (net (code "90") (name "unconnected-(J1-Pad22)") (class "Default")
      (node (ref "J1") (pin "22") (pinfunction "22_22") (pintype "passive+no_connect"))
    )
    (net (code "91") (name "unconnected-(J1-Pad31)") (class "Default")
      (node (ref "J1") (pin "31") (pinfunction "31_31") (pintype "passive+no_connect"))
    )
    (net (code "92") (name "unconnected-(J1-Pad32)") (class "Default")
      (node (ref "J1") (pin "32") (pinfunction "32_32") (pintype "passive+no_connect"))
    )
    (net (code "93") (name "unconnected-(J1-Pad33)") (class "Default")
      (node (ref "J1") (pin "33") (pinfunction "33_33") (pintype "passive+no_connect"))
    )
    (net (code "94") (name "unconnected-(J1-Pad34)") (class "Default")
      (node (ref "J1") (pin "34") (pinfunction "34_34") (pintype "passive+no_connect"))
    )
    (net (code "95") (name "unconnected-(J1-Pad35)") (class "Default")
      (node (ref "J1") (pin "35") (pinfunction "35_35") (pintype "passive+no_connect"))
    )
    (net (code "96") (name "unconnected-(J1-Pad36)") (class "Default")
      (node (ref "J1") (pin "36") (pinfunction "36_36") (pintype "passive+no_connect"))
    )
    (net (code "97") (name "unconnected-(J1-Pad37)") (class "Default")
      (node (ref "J1") (pin "37") (pinfunction "37_37") (pintype "passive+no_connect"))
    )
    (net (code "98") (name "unconnected-(J1-Pad38)") (class "Default")
      (node (ref "J1") (pin "38") (pinfunction "38_38") (pintype "passive+no_connect"))
    )
    (net (code "99") (name "unconnected-(J1-Pad43)") (class "Default")
      (node (ref "J1") (pin "43") (pinfunction "43_43") (pintype "passive+no_connect"))
    )
    (net (code "100") (name "unconnected-(J1-Pad44)") (class "Default")
      (node (ref "J1") (pin "44") (pinfunction "44_44") (pintype "passive+no_connect"))
    )
    (net (code "101") (name "unconnected-(J1-Pad45)") (class "Default")
      (node (ref "J1") (pin "45") (pinfunction "45_45") (pintype "passive+no_connect"))
    )
    (net (code "102") (name "unconnected-(J1-Pad46)") (class "Default")
      (node (ref "J1") (pin "46") (pinfunction "46_46") (pintype "passive+no_connect"))
    )
    (net (code "103") (name "unconnected-(J2-Pad13)") (class "Default")
      (node (ref "J2") (pin "13") (pinfunction "13_13") (pintype "passive+no_connect"))
    )
    (net (code "104") (name "unconnected-(J2-Pad14)") (class "Default")
      (node (ref "J2") (pin "14") (pinfunction "14_14") (pintype "passive+no_connect"))
    )
    (net (code "105") (name "unconnected-(J2-Pad16)") (class "Default")
      (node (ref "J2") (pin "16") (pinfunction "16_16") (pintype "passive+no_connect"))
    )
    (net (code "106") (name "unconnected-(J2-Pad17)") (class "Default")
      (node (ref "J2") (pin "17") (pinfunction "17_17") (pintype "passive+no_connect"))
    )
    (net (code "107") (name "unconnected-(J2-Pad31)") (class "Default")
      (node (ref "J2") (pin "31") (pinfunction "31_31") (pintype "passive+no_connect"))
    )
    (net (code "108") (name "unconnected-(J2-Pad32)") (class "Default")
      (node (ref "J2") (pin "32") (pinfunction "32_32") (pintype "passive+no_connect"))
    )
    (net (code "109") (name "unconnected-(J2-Pad33)") (class "Default")
      (node (ref "J2") (pin "33") (pinfunction "33_33") (pintype "passive+no_connect"))
    )
    (net (code "110") (name "unconnected-(J2-Pad34)") (class "Default")
      (node (ref "J2") (pin "34") (pinfunction "34_34") (pintype "passive+no_connect"))
    )
    (net (code "111") (name "unconnected-(J2-Pad35)") (class "Default")
      (node (ref "J2") (pin "35") (pinfunction "35_35") (pintype "passive+no_connect"))
    )
    (net (code "112") (name "unconnected-(J2-Pad36)") (class "Default")
      (node (ref "J2") (pin "36") (pinfunction "36_36") (pintype "passive+no_connect"))
    )
    (net (code "113") (name "unconnected-(J2-Pad37)") (class "Default")
      (node (ref "J2") (pin "37") (pinfunction "37_37") (pintype "passive+no_connect"))
    )
    (net (code "114") (name "unconnected-(J2-Pad38)") (class "Default")
      (node (ref "J2") (pin "38") (pinfunction "38_38") (pintype "passive+no_connect"))
    )
    (net (code "115") (name "unconnected-(J2-Pad43)") (class "Default")
      (node (ref "J2") (pin "43") (pinfunction "43_43") (pintype "passive+no_connect"))
    )
    (net (code "116") (name "unconnected-(J2-Pad44)") (class "Default")
      (node (ref "J2") (pin "44") (pinfunction "44_44") (pintype "passive+no_connect"))
    )
    (net (code "117") (name "unconnected-(J2-Pad45)") (class "Default")
      (node (ref "J2") (pin "45") (pinfunction "45_45") (pintype "passive+no_connect"))
    )
    (net (code "118") (name "unconnected-(J2-Pad46)") (class "Default")
      (node (ref "J2") (pin "46") (pinfunction "46_46") (pintype "passive+no_connect"))
    )
    (net (code "119") (name "unconnected-(M1B-CAM0_MCLK-Pad116)") (class "Default")
      (node (ref "M1") (pin "116") (pinfunction "CAM0_MCLK_116") (pintype "passive"))
    )
    (net (code "120") (name "unconnected-(M1B-CAM1_MCLK-Pad122)") (class "Default")
      (node (ref "M1") (pin "122") (pinfunction "CAM1_MCLK_122") (pintype "passive"))
    )
    (net (code "121") (name "unconnected-(M1B-DSI_CLK_N-Pad76)") (class "Default")
      (node (ref "M1") (pin "76") (pinfunction "DSI_CLK_N_76") (pintype "passive+no_connect"))
    )
    (net (code "122") (name "unconnected-(M1B-DSI_CLK_P-Pad78)") (class "Default")
      (node (ref "M1") (pin "78") (pinfunction "DSI_CLK_P_78") (pintype "passive+no_connect"))
    )
    (net (code "123") (name "unconnected-(M1B-DSI_D0_N-Pad70)") (class "Default")
      (node (ref "M1") (pin "70") (pinfunction "DSI_D0_N_70") (pintype "passive+no_connect"))
    )
    (net (code "124") (name "unconnected-(M1B-DSI_D0_P-Pad72)") (class "Default")
      (node (ref "M1") (pin "72") (pinfunction "DSI_D0_P_72") (pintype "passive+no_connect"))
    )
    (net (code "125") (name "unconnected-(M1B-DSI_D1_N-Pad82)") (class "Default")
      (node (ref "M1") (pin "82") (pinfunction "DSI_D1_N_82") (pintype "passive+no_connect"))
    )
    (net (code "126") (name "unconnected-(M1B-DSI_D1_P-Pad84)") (class "Default")
      (node (ref "M1") (pin "84") (pinfunction "DSI_D1_P_84") (pintype "passive+no_connect"))
    )
    (net (code "127") (name "unconnected-(P1-Pad1)") (class "Default")
      (node (ref "P1") (pin "1") (pinfunction "1_1") (pintype "passive"))
    )
    (net (code "128") (name "unconnected-(P1-Pad2)") (class "Default")
      (node (ref "P1") (pin "2") (pinfunction "2_2") (pintype "passive"))
    )
    (net (code "129") (name "unconnected-(P1-Pad3)") (class "Default")
      (node (ref "P1") (pin "3") (pinfunction "3_3") (pintype "passive"))
    )
  )
)
